# camera_board.net
KiCad netlist of a schematic drawn in EAGLE
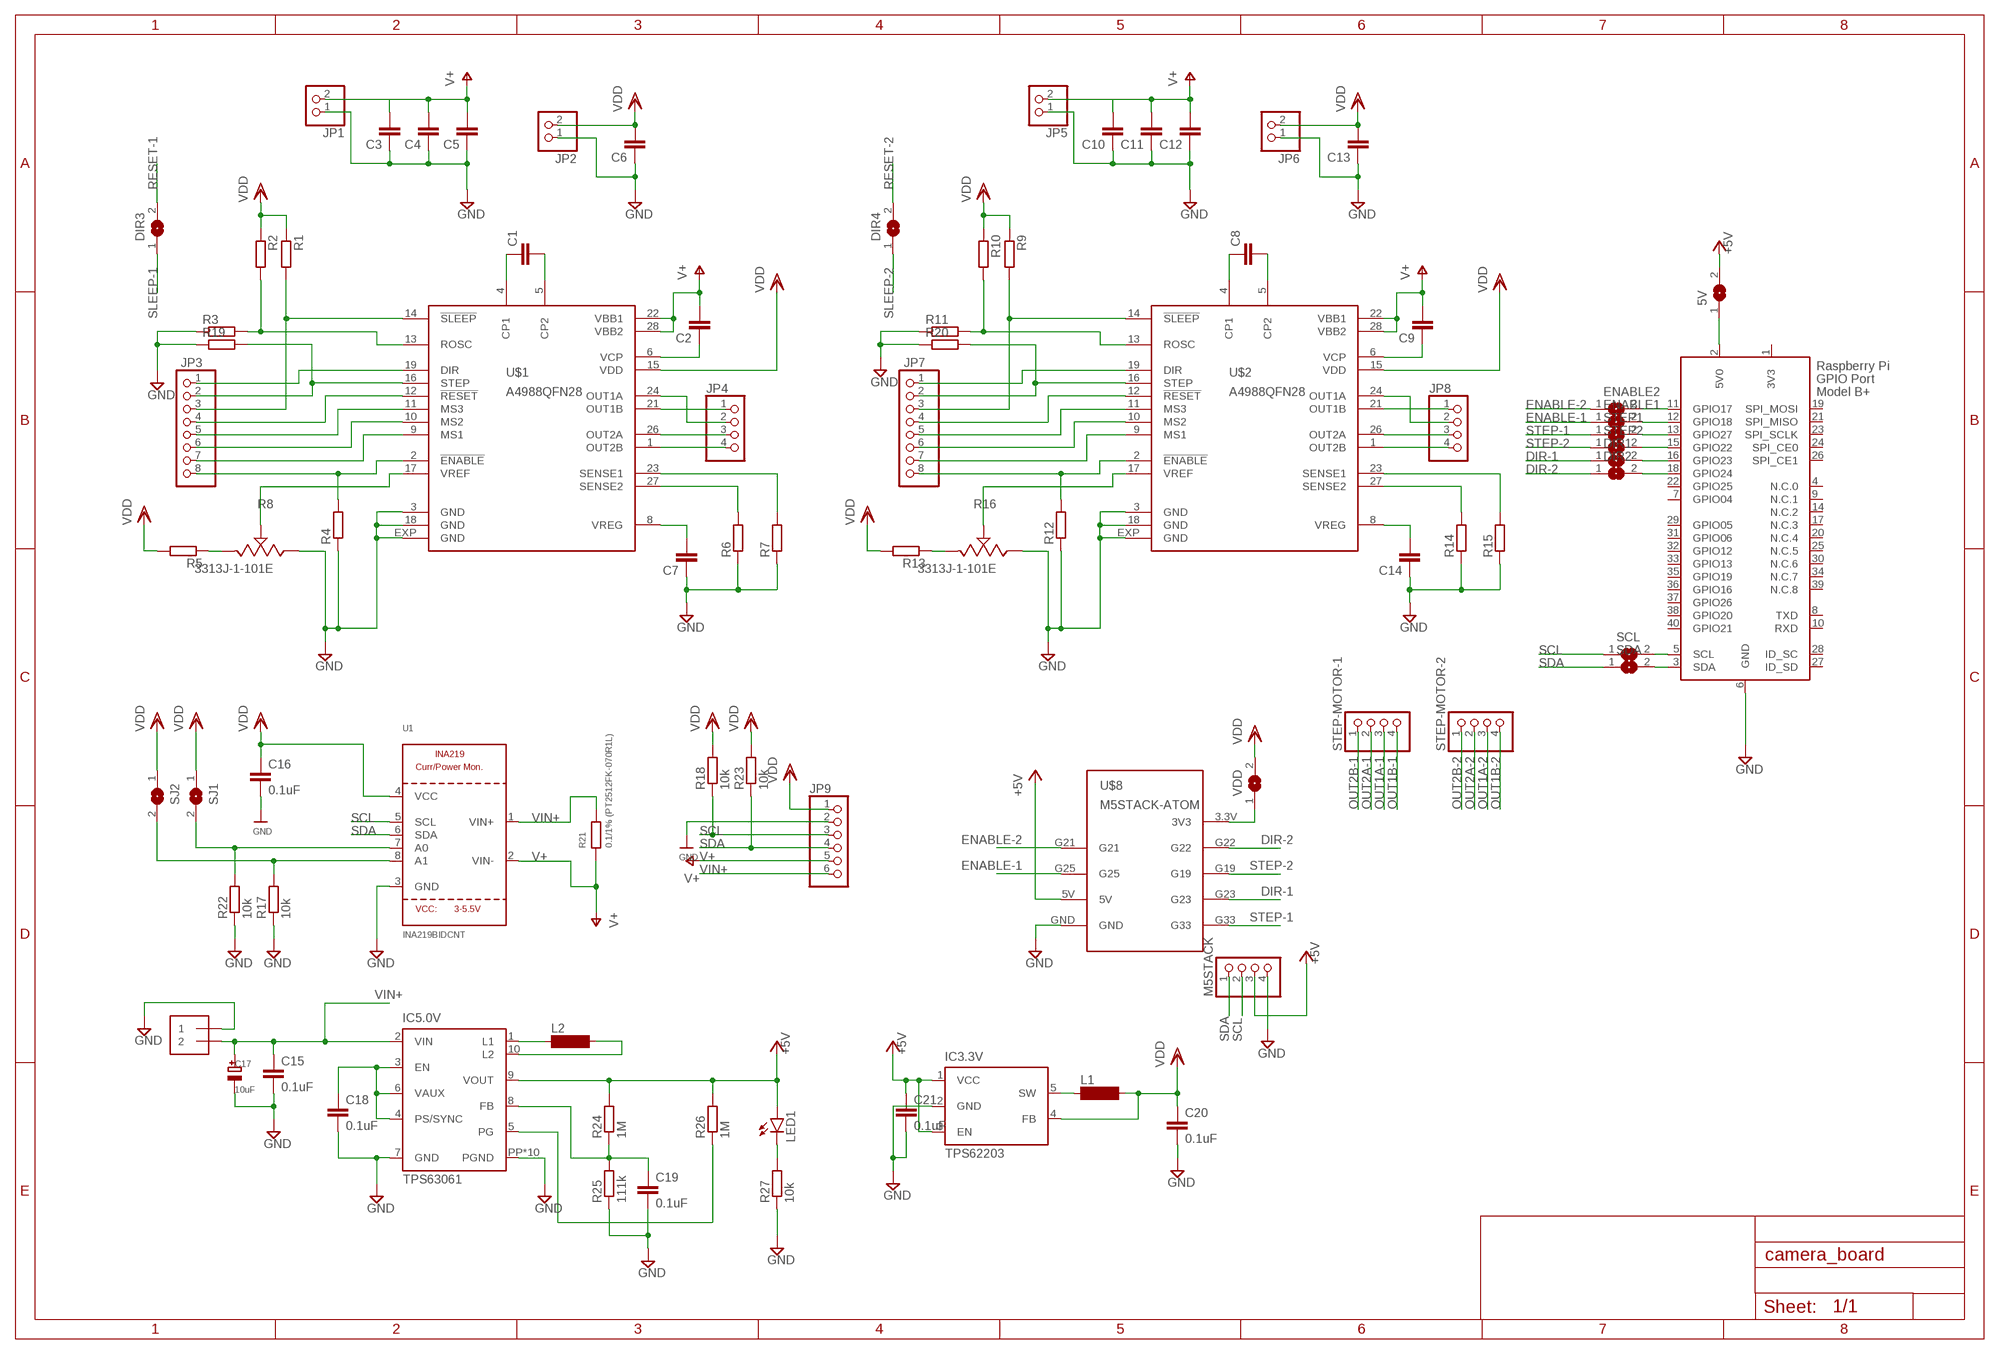
[diagram p0: schematic, sheet 1]

(export (version "E")
  (design (tool "Eeschema 10.0.6"))
  (components
    (comp (ref "5V")
      (value "SOLDERJUMPERREFLOW_NOPASTE")
      (footprint "eagle-import:SOLDERJUMPER_REFLOW_NOPASTE")
      (libsource (lib "eagle-import") (part "SOLDERJUMPERREFLOW_NOPASTE"))
    )
    (comp (ref "7.5V")
      (value "TERMBLOCK_1X2-3.5MM")
      (footprint "eagle-import:1X2-3.5MM")
      (libsource (lib "eagle-import") (part "TERMBLOCK_1X2-3.5MM"))
    )
    (comp (ref "C1")
      (value "C-EUC0402")
      (footprint "eagle-import:C0402")
      (libsource (lib "eagle-import") (part "C-EUC0402"))
    )
    (comp (ref "C2")
      (value "C-EUC0402")
      (footprint "eagle-import:C0402")
      (libsource (lib "eagle-import") (part "C-EUC0402"))
    )
    (comp (ref "C3")
      (value "C-EUC1206")
      (footprint "eagle-import:C1206")
      (libsource (lib "eagle-import") (part "C-EUC1206"))
    )
    (comp (ref "C4")
      (value "C-EUC0402")
      (footprint "eagle-import:C0402")
      (libsource (lib "eagle-import") (part "C-EUC0402"))
    )
    (comp (ref "C5")
      (value "C-EUC0402")
      (footprint "eagle-import:C0402")
      (libsource (lib "eagle-import") (part "C-EUC0402"))
    )
    (comp (ref "C6")
      (value "C-EUC0402")
      (footprint "eagle-import:C0402")
      (libsource (lib "eagle-import") (part "C-EUC0402"))
    )
    (comp (ref "C7")
      (value "C-EUC0402")
      (footprint "eagle-import:C0402")
      (libsource (lib "eagle-import") (part "C-EUC0402"))
    )
    (comp (ref "C8")
      (value "C-EUC0402")
      (footprint "eagle-import:C0402")
      (libsource (lib "eagle-import") (part "C-EUC0402"))
    )
    (comp (ref "C9")
      (value "C-EUC0402")
      (footprint "eagle-import:C0402")
      (libsource (lib "eagle-import") (part "C-EUC0402"))
    )
    (comp (ref "C10")
      (value "C-EUC1206")
      (footprint "eagle-import:C1206")
      (libsource (lib "eagle-import") (part "C-EUC1206"))
    )
    (comp (ref "C11")
      (value "C-EUC0402")
      (footprint "eagle-import:C0402")
      (libsource (lib "eagle-import") (part "C-EUC0402"))
    )
    (comp (ref "C12")
      (value "C-EUC0402")
      (footprint "eagle-import:C0402")
      (libsource (lib "eagle-import") (part "C-EUC0402"))
    )
    (comp (ref "C13")
      (value "C-EUC0402")
      (footprint "eagle-import:C0402")
      (libsource (lib "eagle-import") (part "C-EUC0402"))
    )
    (comp (ref "C14")
      (value "C-EUC0402")
      (footprint "eagle-import:C0402")
      (libsource (lib "eagle-import") (part "C-EUC0402"))
    )
    (comp (ref "C15")
      (value "0.1uF")
      (footprint "eagle-import:C0805")
      (libsource (lib "eagle-import") (part "C-EUC0805"))
    )
    (comp (ref "C16")
      (value "0.1uF")
      (footprint "eagle-import:C0402")
      (libsource (lib "eagle-import") (part "C-EUC0402"))
    )
    (comp (ref "C17")
      (value "10uF")
      (footprint "eagle-import:PANASONIC_C")
      (libsource (lib "eagle-import") (part "CAP_ELECTROLYTICPANASONIC_C"))
    )
    (comp (ref "C18")
      (value "0.1uF")
      (footprint "eagle-import:C0805")
      (libsource (lib "eagle-import") (part "C-EUC0805"))
    )
    (comp (ref "C19")
      (value "0.1uF")
      (footprint "eagle-import:C0805")
      (libsource (lib "eagle-import") (part "C-EUC0805"))
    )
    (comp (ref "C20")
      (value "0.1uF")
      (footprint "eagle-import:C0805")
      (libsource (lib "eagle-import") (part "C-EUC0805"))
    )
    (comp (ref "C21")
      (value "0.1uF")
      (footprint "eagle-import:C0805")
      (libsource (lib "eagle-import") (part "C-EUC0805"))
    )
    (comp (ref "DIR1")
      (value "SOLDERJUMPERREFLOW_NOPASTE")
      (footprint "eagle-import:SOLDERJUMPER_REFLOW_NOPASTE")
      (libsource (lib "eagle-import") (part "SOLDERJUMPERREFLOW_NOPASTE"))
    )
    (comp (ref "DIR2")
      (value "SOLDERJUMPERREFLOW_NOPASTE")
      (footprint "eagle-import:SOLDERJUMPER_REFLOW_NOPASTE")
      (libsource (lib "eagle-import") (part "SOLDERJUMPERREFLOW_NOPASTE"))
    )
    (comp (ref "DIR3")
      (value "SOLDERJUMPERREFLOW_NOPASTE")
      (footprint "eagle-import:SOLDERJUMPER_REFLOW_NOPASTE")
      (libsource (lib "eagle-import") (part "SOLDERJUMPERREFLOW_NOPASTE"))
    )
    (comp (ref "DIR4")
      (value "SOLDERJUMPERREFLOW_NOPASTE")
      (footprint "eagle-import:SOLDERJUMPER_REFLOW_NOPASTE")
      (libsource (lib "eagle-import") (part "SOLDERJUMPERREFLOW_NOPASTE"))
    )
    (comp (ref "ENABLE1")
      (value "SOLDERJUMPERREFLOW_NOPASTE")
      (footprint "eagle-import:SOLDERJUMPER_REFLOW_NOPASTE")
      (libsource (lib "eagle-import") (part "SOLDERJUMPERREFLOW_NOPASTE"))
    )
    (comp (ref "ENABLE2")
      (value "SOLDERJUMPERREFLOW_NOPASTE")
      (footprint "eagle-import:SOLDERJUMPER_REFLOW_NOPASTE")
      (libsource (lib "eagle-import") (part "SOLDERJUMPERREFLOW_NOPASTE"))
    )
    (comp (ref "IC3.3V")
      (value "TPS62203")
      (footprint "eagle-import:SOT23-5")
      (libsource (lib "eagle-import") (part "TPS62203"))
    )
    (comp (ref "IC5.0V")
      (value "TPS63061")
      (footprint "eagle-import:DSC-S-PWSON-N10")
      (libsource (lib "eagle-import") (part "TPS63061"))
    )
    (comp (ref "JP1")
      (value "PINHD-1X2")
      (footprint "eagle-import:1X02")
      (libsource (lib "eagle-import") (part "PINHD-1X2"))
    )
    (comp (ref "JP2")
      (value "PINHD-1X2")
      (footprint "eagle-import:1X02")
      (libsource (lib "eagle-import") (part "PINHD-1X2"))
    )
    (comp (ref "JP3")
      (value "PINHD-1X8")
      (footprint "eagle-import:1X08")
      (libsource (lib "eagle-import") (part "PINHD-1X8"))
    )
    (comp (ref "JP4")
      (value "PINHD-1X4")
      (footprint "eagle-import:1X04")
      (libsource (lib "eagle-import") (part "PINHD-1X4"))
    )
    (comp (ref "JP5")
      (value "PINHD-1X2")
      (footprint "eagle-import:1X02")
      (libsource (lib "eagle-import") (part "PINHD-1X2"))
    )
    (comp (ref "JP6")
      (value "PINHD-1X2")
      (footprint "eagle-import:1X02")
      (libsource (lib "eagle-import") (part "PINHD-1X2"))
    )
    (comp (ref "JP7")
      (value "PINHD-1X8")
      (footprint "eagle-import:1X08")
      (libsource (lib "eagle-import") (part "PINHD-1X8"))
    )
    (comp (ref "JP8")
      (value "PINHD-1X4")
      (footprint "eagle-import:1X04")
      (libsource (lib "eagle-import") (part "PINHD-1X4"))
    )
    (comp (ref "JP9")
      (value "HEADER-1X670MIL")
      (footprint "eagle-import:1X06_ROUND_70")
      (libsource (lib "eagle-import") (part "HEADER-1X670MIL"))
    )
    (comp (ref "L1")
      (value "MS50")
      (footprint "eagle-import:MS50")
      (libsource (lib "eagle-import") (part "MS50"))
    )
    (comp (ref "L2")
      (value "MS50")
      (footprint "eagle-import:MS50")
      (libsource (lib "eagle-import") (part "MS50"))
    )
    (comp (ref "LED1")
      (value "LEDCHIPLED_0603")
      (footprint "eagle-import:CHIPLED_0603")
      (libsource (lib "eagle-import") (part "LEDCHIPLED_0603"))
    )
    (comp (ref "M5STACK")
      (value "PINHD-1X4")
      (footprint "eagle-import:1X04")
      (libsource (lib "eagle-import") (part "PINHD-1X4"))
    )
    (comp (ref "R1")
      (value "R-EU_R0402")
      (footprint "eagle-import:R0402")
      (libsource (lib "eagle-import") (part "R-EU_R0402"))
    )
    (comp (ref "R2")
      (value "R-EU_R0402")
      (footprint "eagle-import:R0402")
      (libsource (lib "eagle-import") (part "R-EU_R0402"))
    )
    (comp (ref "R3")
      (value "R-EU_R0402")
      (footprint "eagle-import:R0402")
      (libsource (lib "eagle-import") (part "R-EU_R0402"))
    )
    (comp (ref "R4")
      (value "R-EU_R0402")
      (footprint "eagle-import:R0402")
      (libsource (lib "eagle-import") (part "R-EU_R0402"))
    )
    (comp (ref "R5")
      (value "R-EU_R0402")
      (footprint "eagle-import:R0402")
      (libsource (lib "eagle-import") (part "R-EU_R0402"))
    )
    (comp (ref "R6")
      (value "R-EU_R0603")
      (footprint "eagle-import:R0603")
      (libsource (lib "eagle-import") (part "R-EU_R0603"))
    )
    (comp (ref "R7")
      (value "R-EU_R0603")
      (footprint "eagle-import:R0603")
      (libsource (lib "eagle-import") (part "R-EU_R0603"))
    )
    (comp (ref "R8")
      (value "3313J-1-101E")
      (footprint "eagle-import:3313J-1-101E")
      (fields (field (name "MANUFACTURER") "Bourns Inc.") (field (name "CREATED_BY") "PCBLayout.com"))
      (libsource (lib "eagle-import") (part "3313J-1-101E"))
    )
    (comp (ref "R9")
      (value "R-EU_R0402")
      (footprint "eagle-import:R0402")
      (libsource (lib "eagle-import") (part "R-EU_R0402"))
    )
    (comp (ref "R10")
      (value "R-EU_R0402")
      (footprint "eagle-import:R0402")
      (libsource (lib "eagle-import") (part "R-EU_R0402"))
    )
    (comp (ref "R11")
      (value "R-EU_R0402")
      (footprint "eagle-import:R0402")
      (libsource (lib "eagle-import") (part "R-EU_R0402"))
    )
    (comp (ref "R12")
      (value "R-EU_R0402")
      (footprint "eagle-import:R0402")
      (libsource (lib "eagle-import") (part "R-EU_R0402"))
    )
    (comp (ref "R13")
      (value "R-EU_R0402")
      (footprint "eagle-import:R0402")
      (libsource (lib "eagle-import") (part "R-EU_R0402"))
    )
    (comp (ref "R14")
      (value "R-EU_R0603")
      (footprint "eagle-import:R0603")
      (libsource (lib "eagle-import") (part "R-EU_R0603"))
    )
    (comp (ref "R15")
      (value "R-EU_R0603")
      (footprint "eagle-import:R0603")
      (libsource (lib "eagle-import") (part "R-EU_R0603"))
    )
    (comp (ref "R16")
      (value "3313J-1-101E")
      (footprint "eagle-import:3313J-1-101E")
      (fields (field (name "MANUFACTURER") "Bourns Inc.") (field (name "CREATED_BY") "PCBLayout.com"))
      (libsource (lib "eagle-import") (part "3313J-1-101E"))
    )
    (comp (ref "R17")
      (value "10k")
      (footprint "eagle-import:R0603")
      (libsource (lib "eagle-import") (part "R-EU_R0603"))
    )
    (comp (ref "R18")
      (value "10k")
      (footprint "eagle-import:R0603")
      (libsource (lib "eagle-import") (part "R-EU_R0603"))
    )
    (comp (ref "R19")
      (value "R-EU_R0805")
      (footprint "eagle-import:R0805")
      (libsource (lib "eagle-import") (part "R-EU_R0805"))
    )
    (comp (ref "R20")
      (value "R-EU_R0805")
      (footprint "eagle-import:R0805")
      (libsource (lib "eagle-import") (part "R-EU_R0805"))
    )
    (comp (ref "R21")
      (value "0.1/1% (PT2512FK-070R1L)")
      (footprint "eagle-import:R2512")
      (libsource (lib "eagle-import") (part "R-EU_R2512"))
    )
    (comp (ref "R22")
      (value "10k")
      (footprint "eagle-import:R0603")
      (libsource (lib "eagle-import") (part "R-EU_R0603"))
    )
    (comp (ref "R23")
      (value "10k")
      (footprint "eagle-import:R0603")
      (libsource (lib "eagle-import") (part "R-EU_R0603"))
    )
    (comp (ref "R24")
      (value "1M")
      (footprint "eagle-import:R0603")
      (libsource (lib "eagle-import") (part "R-EU_R0603"))
    )
    (comp (ref "R25")
      (value "111k")
      (footprint "eagle-import:R0603")
      (libsource (lib "eagle-import") (part "R-EU_R0603"))
    )
    (comp (ref "R26")
      (value "1M")
      (footprint "eagle-import:R0603")
      (libsource (lib "eagle-import") (part "R-EU_R0603"))
    )
    (comp (ref "R27")
      (value "10k")
      (footprint "eagle-import:R0603")
      (libsource (lib "eagle-import") (part "R-EU_R0603"))
    )
    (comp (ref "SCL")
      (value "SOLDERJUMPERREFLOW_NOPASTE")
      (footprint "eagle-import:SOLDERJUMPER_REFLOW_NOPASTE")
      (libsource (lib "eagle-import") (part "SOLDERJUMPERREFLOW_NOPASTE"))
    )
    (comp (ref "SDA")
      (value "SOLDERJUMPERREFLOW_NOPASTE")
      (footprint "eagle-import:SOLDERJUMPER_REFLOW_NOPASTE")
      (libsource (lib "eagle-import") (part "SOLDERJUMPERREFLOW_NOPASTE"))
    )
    (comp (ref "SJ1")
      (value "SOLDERJUMPERREFLOW_NOPASTE")
      (footprint "eagle-import:SOLDERJUMPER_REFLOW_NOPASTE")
      (libsource (lib "eagle-import") (part "SOLDERJUMPERREFLOW_NOPASTE"))
    )
    (comp (ref "SJ2")
      (value "SOLDERJUMPERREFLOW_NOPASTE")
      (footprint "eagle-import:SOLDERJUMPER_REFLOW_NOPASTE")
      (libsource (lib "eagle-import") (part "SOLDERJUMPERREFLOW_NOPASTE"))
    )
    (comp (ref "STEP-MOTOR-1")
      (value "PINHD-1X4")
      (footprint "eagle-import:1X04")
      (libsource (lib "eagle-import") (part "PINHD-1X4"))
    )
    (comp (ref "STEP-MOTOR-2")
      (value "PINHD-1X4")
      (footprint "eagle-import:1X04")
      (libsource (lib "eagle-import") (part "PINHD-1X4"))
    )
    (comp (ref "STEP1")
      (value "SOLDERJUMPERREFLOW_NOPASTE")
      (footprint "eagle-import:SOLDERJUMPER_REFLOW_NOPASTE")
      (libsource (lib "eagle-import") (part "SOLDERJUMPERREFLOW_NOPASTE"))
    )
    (comp (ref "STEP2")
      (value "SOLDERJUMPERREFLOW_NOPASTE")
      (footprint "eagle-import:SOLDERJUMPER_REFLOW_NOPASTE")
      (libsource (lib "eagle-import") (part "SOLDERJUMPERREFLOW_NOPASTE"))
    )
    (comp (ref "U$1")
      (value "A4988QFN28")
      (footprint "eagle-import:QFN28-ML_6X6MM")
      (libsource (lib "eagle-import") (part "A4988QFN28"))
    )
    (comp (ref "U$2")
      (value "A4988QFN28")
      (footprint "eagle-import:QFN28-ML_6X6MM")
      (libsource (lib "eagle-import") (part "A4988QFN28"))
    )
    (comp (ref "U$8")
      (value "M5STACK-ATOM")
      (footprint "eagle-import:M5STACK-ATOM")
      (libsource (lib "eagle-import") (part "M5STACK-ATOM"))
    )
    (comp (ref "U1")
      (value "INA219BIDCNT")
      (footprint "eagle-import:SOT23-8")
      (libsource (lib "eagle-import") (part "INA219"))
    )
    (comp (ref "VDD")
      (value "SOLDERJUMPERREFLOW_NOPASTE")
      (footprint "eagle-import:SOLDERJUMPER_REFLOW_NOPASTE")
      (libsource (lib "eagle-import") (part "SOLDERJUMPERREFLOW_NOPASTE"))
    )
    (comp (ref "X1")
      (value "RASPI_BOARD_B+_E4")
      (footprint "eagle-import:RASPI_BOARD_B+_EDGES_4DRILL")
      (libsource (lib "eagle-import") (part "RASPI_BOARD_B+_E4"))
    )
  )
  (nets
    (net (code "1") (name "+5V") (class "Default")
      (node (ref "5V") (pin "2") (pinfunction "2_2") (pintype "passive"))
      (node (ref "C21") (pin "1") (pinfunction "1_1") (pintype "passive"))
      (node (ref "IC3.3V") (pin "1") (pinfunction "VCC_1") (pintype "power_in"))
      (node (ref "IC3.3V") (pin "3") (pinfunction "EN_3") (pintype "input"))
      (node (ref "IC5.0V") (pin "9") (pinfunction "VOUT_9") (pintype "output"))
      (node (ref "LED1") (pin "A") (pinfunction "A_A") (pintype "passive"))
      (node (ref "M5STACK") (pin "3") (pinfunction "3_3") (pintype "passive"))
      (node (ref "R24") (pin "2") (pinfunction "2_2") (pintype "passive"))
      (node (ref "R26") (pin "2") (pinfunction "2_2") (pintype "passive"))
      (node (ref "U$8") (pin "5V") (pinfunction "5V_5V") (pintype "bidirectional"))
    )
    (net (code "2") (name "/3V3") (class "Default")
      (node (ref "X1") (pin "1") (pinfunction "3V3_1") (pintype "power_in"))
    )
    (net (code "3") (name "/DIR-1") (class "Default")
      (node (ref "DIR1") (pin "1") (pinfunction "1_1") (pintype "passive"))
      (node (ref "JP3") (pin "1") (pinfunction "1_1") (pintype "passive"))
      (node (ref "U$1") (pin "19") (pinfunction "DIR_19") (pintype "bidirectional"))
      (node (ref "U$8") (pin "G23") (pinfunction "G23_G23") (pintype "bidirectional"))
    )
    (net (code "4") (name "/DIR-2") (class "Default")
      (node (ref "DIR2") (pin "1") (pinfunction "1_1") (pintype "passive"))
      (node (ref "JP7") (pin "1") (pinfunction "1_1") (pintype "passive"))
      (node (ref "U$2") (pin "19") (pinfunction "DIR_19") (pintype "bidirectional"))
      (node (ref "U$8") (pin "G22") (pinfunction "G22_G22") (pintype "bidirectional"))
    )
    (net (code "5") (name "/ENABLE-1") (class "Default")
      (node (ref "ENABLE1") (pin "1") (pinfunction "1_1") (pintype "passive"))
      (node (ref "JP3") (pin "8") (pinfunction "8_8") (pintype "passive"))
      (node (ref "R4") (pin "2") (pinfunction "2_2") (pintype "passive"))
      (node (ref "U$1") (pin "2") (pinfunction "~{ENABLE}_2") (pintype "bidirectional"))
      (node (ref "U$8") (pin "G25") (pinfunction "G25_G25") (pintype "bidirectional"))
    )
    (net (code "6") (name "/ENABLE-2") (class "Default")
      (node (ref "ENABLE2") (pin "1") (pinfunction "1_1") (pintype "passive"))
      (node (ref "JP7") (pin "8") (pinfunction "8_8") (pintype "passive"))
      (node (ref "R12") (pin "2") (pinfunction "2_2") (pintype "passive"))
      (node (ref "U$2") (pin "2") (pinfunction "~{ENABLE}_2") (pintype "bidirectional"))
      (node (ref "U$8") (pin "G21") (pinfunction "G21_G21") (pintype "bidirectional"))
    )
    (net (code "7") (name "/OUT1A-1") (class "Default")
      (node (ref "JP4") (pin "2") (pinfunction "2_2") (pintype "passive"))
      (node (ref "STEP-MOTOR-1") (pin "3") (pinfunction "3_3") (pintype "passive"))
      (node (ref "U$1") (pin "24") (pinfunction "OUT1A_24") (pintype "output"))
    )
    (net (code "8") (name "/OUT1A-2") (class "Default")
      (node (ref "JP8") (pin "2") (pinfunction "2_2") (pintype "passive"))
      (node (ref "STEP-MOTOR-2") (pin "3") (pinfunction "3_3") (pintype "passive"))
      (node (ref "U$2") (pin "24") (pinfunction "OUT1A_24") (pintype "output"))
    )
    (net (code "9") (name "/OUT1B-1") (class "Default")
      (node (ref "JP4") (pin "1") (pinfunction "1_1") (pintype "passive"))
      (node (ref "STEP-MOTOR-1") (pin "4") (pinfunction "4_4") (pintype "passive"))
      (node (ref "U$1") (pin "21") (pinfunction "OUT1B_21") (pintype "output"))
    )
    (net (code "10") (name "/OUT1B-2") (class "Default")
      (node (ref "JP8") (pin "1") (pinfunction "1_1") (pintype "passive"))
      (node (ref "STEP-MOTOR-2") (pin "4") (pinfunction "4_4") (pintype "passive"))
      (node (ref "U$2") (pin "21") (pinfunction "OUT1B_21") (pintype "output"))
    )
    (net (code "11") (name "/OUT2A-1") (class "Default")
      (node (ref "JP4") (pin "3") (pinfunction "3_3") (pintype "passive"))
      (node (ref "STEP-MOTOR-1") (pin "2") (pinfunction "2_2") (pintype "passive"))
      (node (ref "U$1") (pin "26") (pinfunction "OUT2A_26") (pintype "output"))
    )
    (net (code "12") (name "/OUT2A-2") (class "Default")
      (node (ref "JP8") (pin "3") (pinfunction "3_3") (pintype "passive"))
      (node (ref "STEP-MOTOR-2") (pin "2") (pinfunction "2_2") (pintype "passive"))
      (node (ref "U$2") (pin "26") (pinfunction "OUT2A_26") (pintype "output"))
    )
    (net (code "13") (name "/OUT2B-1") (class "Default")
      (node (ref "JP4") (pin "4") (pinfunction "4_4") (pintype "passive"))
      (node (ref "STEP-MOTOR-1") (pin "1") (pinfunction "1_1") (pintype "passive"))
      (node (ref "U$1") (pin "1") (pinfunction "OUT2B_1") (pintype "output"))
    )
    (net (code "14") (name "/OUT2B-2") (class "Default")
      (node (ref "JP8") (pin "4") (pinfunction "4_4") (pintype "passive"))
      (node (ref "STEP-MOTOR-2") (pin "1") (pinfunction "1_1") (pintype "passive"))
      (node (ref "U$2") (pin "1") (pinfunction "OUT2B_1") (pintype "output"))
    )
    (net (code "15") (name "/RESET-1") (class "Default")
      (node (ref "DIR3") (pin "2") (pinfunction "2_2") (pintype "passive"))
      (node (ref "JP3") (pin "4") (pinfunction "4_4") (pintype "passive"))
      (node (ref "U$1") (pin "12") (pinfunction "~{RESET}_12") (pintype "bidirectional"))
    )
    (net (code "16") (name "/RESET-2") (class "Default")
      (node (ref "DIR4") (pin "2") (pinfunction "2_2") (pintype "passive"))
      (node (ref "JP7") (pin "4") (pinfunction "4_4") (pintype "passive"))
      (node (ref "U$2") (pin "12") (pinfunction "~{RESET}_12") (pintype "bidirectional"))
    )
    (net (code "17") (name "/SCL") (class "Default")
      (node (ref "JP9") (pin "3") (pinfunction "3_3") (pintype "passive"))
      (node (ref "M5STACK") (pin "2") (pinfunction "2_2") (pintype "passive"))
      (node (ref "R18") (pin "1") (pinfunction "1_1") (pintype "passive"))
      (node (ref "SCL") (pin "1") (pinfunction "1_1") (pintype "passive"))
      (node (ref "U1") (pin "5") (pinfunction "SCL_5") (pintype "bidirectional"))
    )
    (net (code "18") (name "/SDA") (class "Default")
      (node (ref "JP9") (pin "4") (pinfunction "4_4") (pintype "passive"))
      (node (ref "M5STACK") (pin "1") (pinfunction "1_1") (pintype "passive"))
      (node (ref "R23") (pin "1") (pinfunction "1_1") (pintype "passive"))
      (node (ref "SDA") (pin "1") (pinfunction "1_1") (pintype "passive"))
      (node (ref "U1") (pin "6") (pinfunction "SDA_6") (pintype "bidirectional"))
    )
    (net (code "19") (name "/SLEEP-1") (class "Default")
      (node (ref "DIR3") (pin "1") (pinfunction "1_1") (pintype "passive"))
      (node (ref "JP3") (pin "3") (pinfunction "3_3") (pintype "passive"))
      (node (ref "R1") (pin "2") (pinfunction "2_2") (pintype "passive"))
      (node (ref "U$1") (pin "14") (pinfunction "~{SLEEP}_14") (pintype "bidirectional"))
    )
    (net (code "20") (name "/SLEEP-2") (class "Default")
      (node (ref "DIR4") (pin "1") (pinfunction "1_1") (pintype "passive"))
      (node (ref "JP7") (pin "3") (pinfunction "3_3") (pintype "passive"))
      (node (ref "R9") (pin "2") (pinfunction "2_2") (pintype "passive"))
      (node (ref "U$2") (pin "14") (pinfunction "~{SLEEP}_14") (pintype "bidirectional"))
    )
    (net (code "21") (name "/STEP-1") (class "Default")
      (node (ref "JP3") (pin "2") (pinfunction "2_2") (pintype "passive"))
      (node (ref "R19") (pin "2") (pinfunction "2_2") (pintype "passive"))
      (node (ref "STEP1") (pin "1") (pinfunction "1_1") (pintype "passive"))
      (node (ref "U$1") (pin "16") (pinfunction "STEP_16") (pintype "output"))
      (node (ref "U$8") (pin "G33") (pinfunction "G33_G33") (pintype "bidirectional"))
    )
    (net (code "22") (name "/STEP-2") (class "Default")
      (node (ref "JP7") (pin "2") (pinfunction "2_2") (pintype "passive"))
      (node (ref "R20") (pin "2") (pinfunction "2_2") (pintype "passive"))
      (node (ref "STEP2") (pin "1") (pinfunction "1_1") (pintype "passive"))
      (node (ref "U$2") (pin "16") (pinfunction "STEP_16") (pintype "output"))
      (node (ref "U$8") (pin "G19") (pinfunction "G19_G19") (pintype "bidirectional"))
    )
    (net (code "23") (name "/VIN+") (class "Default")
      (node (ref "7.5V") (pin "2") (pinfunction "2_2") (pintype "passive"))
      (node (ref "C15") (pin "1") (pinfunction "1_1") (pintype "passive"))
      (node (ref "C17") (pin "+") (pinfunction "+_+") (pintype "passive"))
      (node (ref "IC5.0V") (pin "2") (pinfunction "VIN_2") (pintype "input"))
      (node (ref "JP9") (pin "6") (pinfunction "6_6") (pintype "passive"))
      (node (ref "R21") (pin "2") (pinfunction "2_2") (pintype "passive"))
      (node (ref "U1") (pin "1") (pinfunction "VIN+_1") (pintype "bidirectional"))
    )
    (net (code "24") (name "GND") (class "Default")
      (node (ref "7.5V") (pin "1") (pinfunction "1_1") (pintype "passive"))
      (node (ref "C10") (pin "1") (pinfunction "1_1") (pintype "passive"))
      (node (ref "C11") (pin "1") (pinfunction "1_1") (pintype "passive"))
      (node (ref "C12") (pin "1") (pinfunction "1_1") (pintype "passive"))
      (node (ref "C13") (pin "1") (pinfunction "1_1") (pintype "passive"))
      (node (ref "C14") (pin "1") (pinfunction "1_1") (pintype "passive"))
      (node (ref "C15") (pin "2") (pinfunction "2_2") (pintype "passive"))
      (node (ref "C16") (pin "2") (pinfunction "2_2") (pintype "passive"))
      (node (ref "C17") (pin "-") (pinfunction "-_-") (pintype "passive"))
      (node (ref "C18") (pin "2") (pinfunction "2_2") (pintype "passive"))
      (node (ref "C19") (pin "2") (pinfunction "2_2") (pintype "passive"))
      (node (ref "C20") (pin "2") (pinfunction "2_2") (pintype "passive"))
      (node (ref "C21") (pin "2") (pinfunction "2_2") (pintype "passive"))
      (node (ref "C3") (pin "1") (pinfunction "1_1") (pintype "passive"))
      (node (ref "C4") (pin "1") (pinfunction "1_1") (pintype "passive"))
      (node (ref "C5") (pin "1") (pinfunction "1_1") (pintype "passive"))
      (node (ref "C6") (pin "1") (pinfunction "1_1") (pintype "passive"))
      (node (ref "C7") (pin "1") (pinfunction "1_1") (pintype "passive"))
      (node (ref "IC3.3V") (pin "2") (pinfunction "GND_2") (pintype "power_in"))
      (node (ref "IC5.0V") (pin "7") (pinfunction "GND_7") (pintype "input"))
      (node (ref "IC5.0V") (pin "PP") (pinfunction "PGND_PP") (pintype "power_in"))
      (node (ref "IC5.0V") (pin "PP@1") (pinfunction "PGND_PP@1") (pintype "power_in"))
      (node (ref "IC5.0V") (pin "PP@10") (pinfunction "PGND_PP@10") (pintype "power_in"))
      (node (ref "IC5.0V") (pin "PP@2") (pinfunction "PGND_PP@2") (pintype "power_in"))
      (node (ref "IC5.0V") (pin "PP@3") (pinfunction "PGND_PP@3") (pintype "power_in"))
      (node (ref "IC5.0V") (pin "PP@4") (pinfunction "PGND_PP@4") (pintype "power_in"))
      (node (ref "IC5.0V") (pin "PP@5") (pinfunction "PGND_PP@5") (pintype "power_in"))
      (node (ref "IC5.0V") (pin "PP@7") (pinfunction "PGND_PP@7") (pintype "power_in"))
      (node (ref "IC5.0V") (pin "PP@8") (pinfunction "PGND_PP@8") (pintype "power_in"))
      (node (ref "IC5.0V") (pin "PP@9") (pinfunction "PGND_PP@9") (pintype "power_in"))
      (node (ref "JP1") (pin "1") (pinfunction "1_1") (pintype "passive"))
      (node (ref "JP2") (pin "1") (pinfunction "1_1") (pintype "passive"))
      (node (ref "JP5") (pin "1") (pinfunction "1_1") (pintype "passive"))
      (node (ref "JP6") (pin "1") (pinfunction "1_1") (pintype "passive"))
      (node (ref "JP9") (pin "2") (pinfunction "2_2") (pintype "passive"))
      (node (ref "M5STACK") (pin "4") (pinfunction "4_4") (pintype "passive"))
      (node (ref "R11") (pin "1") (pinfunction "1_1") (pintype "passive"))
      (node (ref "R12") (pin "1") (pinfunction "1_1") (pintype "passive"))
      (node (ref "R14") (pin "1") (pinfunction "1_1") (pintype "passive"))
      (node (ref "R15") (pin "1") (pinfunction "1_1") (pintype "passive"))
      (node (ref "R16") (pin "3") (pinfunction "3_3") (pintype "passive"))
      (node (ref "R17") (pin "1") (pinfunction "1_1") (pintype "passive"))
      (node (ref "R19") (pin "1") (pinfunction "1_1") (pintype "passive"))
      (node (ref "R20") (pin "1") (pinfunction "1_1") (pintype "passive"))
      (node (ref "R22") (pin "1") (pinfunction "1_1") (pintype "passive"))
      (node (ref "R25") (pin "1") (pinfunction "1_1") (pintype "passive"))
      (node (ref "R27") (pin "1") (pinfunction "1_1") (pintype "passive"))
      (node (ref "R3") (pin "1") (pinfunction "1_1") (pintype "passive"))
      (node (ref "R4") (pin "1") (pinfunction "1_1") (pintype "passive"))
      (node (ref "R6") (pin "1") (pinfunction "1_1") (pintype "passive"))
      (node (ref "R7") (pin "1") (pinfunction "1_1") (pintype "passive"))
      (node (ref "R8") (pin "3") (pinfunction "3_3") (pintype "passive"))
      (node (ref "U$1") (pin "18") (pinfunction "GND_18") (pintype "power_in"))
      (node (ref "U$1") (pin "3") (pinfunction "GND_3") (pintype "power_in"))
      (node (ref "U$1") (pin "EXP") (pinfunction "GND_EXP") (pintype "power_in"))
      (node (ref "U$2") (pin "18") (pinfunction "GND_18") (pintype "power_in"))
      (node (ref "U$2") (pin "3") (pinfunction "GND_3") (pintype "power_in"))
      (node (ref "U$2") (pin "EXP") (pinfunction "GND_EXP") (pintype "power_in"))
      (node (ref "U$8") (pin "GND") (pinfunction "GND_GND") (pintype "bidirectional"))
      (node (ref "U1") (pin "3") (pinfunction "GND_3") (pintype "bidirectional"))
      (node (ref "X1") (pin "6") (pinfunction "GND_6") (pintype "power_in"))
    )
    (net (code "25") (name "Net-(IC3.3V-SW)") (class "Default")
      (node (ref "IC3.3V") (pin "5") (pinfunction "SW_5") (pintype "output"))
      (node (ref "L1") (pin "1") (pinfunction "1_1") (pintype "passive"))
    )
    (net (code "26") (name "Net-(IC5.0V-EN)") (class "Default")
      (node (ref "C18") (pin "1") (pinfunction "1_1") (pintype "passive"))
      (node (ref "IC5.0V") (pin "3") (pinfunction "EN_3") (pintype "input"))
      (node (ref "IC5.0V") (pin "4") (pinfunction "PS/SYNC_4") (pintype "input"))
      (node (ref "IC5.0V") (pin "6") (pinfunction "VAUX_6") (pintype "power_in"))
    )
    (net (code "27") (name "Net-(IC5.0V-FB)") (class "Default")
      (node (ref "C19") (pin "1") (pinfunction "1_1") (pintype "passive"))
      (node (ref "IC5.0V") (pin "8") (pinfunction "FB_8") (pintype "input"))
      (node (ref "R24") (pin "1") (pinfunction "1_1") (pintype "passive"))
      (node (ref "R25") (pin "2") (pinfunction "2_2") (pintype "passive"))
    )
    (net (code "28") (name "Net-(IC5.0V-L1)") (class "Default")
      (node (ref "IC5.0V") (pin "1") (pinfunction "L1_1") (pintype "input"))
      (node (ref "L2") (pin "1") (pinfunction "1_1") (pintype "passive"))
    )
    (net (code "29") (name "Net-(IC5.0V-L2)") (class "Default")
      (node (ref "IC5.0V") (pin "10") (pinfunction "L2_10") (pintype "input"))
      (node (ref "L2") (pin "2") (pinfunction "2_2") (pintype "passive"))
    )
    (net (code "30") (name "Net-(IC5.0V-PG)") (class "Default")
      (node (ref "IC5.0V") (pin "5") (pinfunction "PG_5") (pintype "output"))
      (node (ref "R26") (pin "1") (pinfunction "1_1") (pintype "passive"))
    )
    (net (code "31") (name "Net-(LED1-PadC)") (class "Default")
      (node (ref "LED1") (pin "C") (pinfunction "C_C") (pintype "passive"))
      (node (ref "R27") (pin "2") (pinfunction "2_2") (pintype "passive"))
    )
    (net (code "32") (name "Net-(R5-Pad1)") (class "Default")
      (node (ref "R5") (pin "1") (pinfunction "1_1") (pintype "passive"))
      (node (ref "R8") (pin "1") (pinfunction "1_1") (pintype "passive"))
    )
    (net (code "33") (name "Net-(R13-Pad1)") (class "Default")
      (node (ref "R13") (pin "1") (pinfunction "1_1") (pintype "passive"))
      (node (ref "R16") (pin "1") (pinfunction "1_1") (pintype "passive"))
    )
    (net (code "34") (name "Net-(U$1-CP1)") (class "Default")
      (node (ref "C1") (pin "1") (pinfunction "1_1") (pintype "passive"))
      (node (ref "U$1") (pin "4") (pinfunction "CP1_4") (pintype "bidirectional"))
    )
    (net (code "35") (name "Net-(U$1-CP2)") (class "Default")
      (node (ref "C1") (pin "2") (pinfunction "2_2") (pintype "passive"))
      (node (ref "U$1") (pin "5") (pinfunction "CP2_5") (pintype "bidirectional"))
    )
    (net (code "36") (name "Net-(U$1-MS1)") (class "Default")
      (node (ref "JP3") (pin "7") (pinfunction "7_7") (pintype "passive"))
      (node (ref "U$1") (pin "9") (pinfunction "MS1_9") (pintype "bidirectional"))
    )
    (net (code "37") (name "Net-(U$1-MS2)") (class "Default")
      (node (ref "JP3") (pin "6") (pinfunction "6_6") (pintype "passive"))
      (node (ref "U$1") (pin "10") (pinfunction "MS2_10") (pintype "input"))
    )
    (net (code "38") (name "Net-(U$1-MS3)") (class "Default")
      (node (ref "JP3") (pin "5") (pinfunction "5_5") (pintype "passive"))
      (node (ref "U$1") (pin "11") (pinfunction "MS3_11") (pintype "bidirectional"))
    )
    (net (code "39") (name "Net-(U$1-ROSC)") (class "Default")
      (node (ref "R2") (pin "2") (pinfunction "2_2") (pintype "passive"))
      (node (ref "R3") (pin "2") (pinfunction "2_2") (pintype "passive"))
      (node (ref "U$1") (pin "13") (pinfunction "ROSC_13") (pintype "bidirectional"))
    )
    (net (code "40") (name "Net-(U$1-SENSE1)") (class "Default")
      (node (ref "R7") (pin "2") (pinfunction "2_2") (pintype "passive"))
      (node (ref "U$1") (pin "23") (pinfunction "SENSE1_23") (pintype "input"))
    )
    (net (code "41") (name "Net-(U$1-SENSE2)") (class "Default")
      (node (ref "R6") (pin "2") (pinfunction "2_2") (pintype "passive"))
      (node (ref "U$1") (pin "27") (pinfunction "SENSE2_27") (pintype "bidirectional"))
    )
    (net (code "42") (name "Net-(U$1-VCP)") (class "Default")
      (node (ref "C2") (pin "1") (pinfunction "1_1") (pintype "passive"))
      (node (ref "U$1") (pin "6") (pinfunction "VCP_6") (pintype "power_in"))
    )
    (net (code "43") (name "Net-(U$1-VREF)") (class "Default")
      (node (ref "R8") (pin "2") (pinfunction "2_2") (pintype "passive"))
      (node (ref "U$1") (pin "17") (pinfunction "VREF_17") (pintype "power_in"))
    )
    (net (code "44") (name "Net-(U$1-VREG)") (class "Default")
      (node (ref "C7") (pin "2") (pinfunction "2_2") (pintype "passive"))
      (node (ref "U$1") (pin "8") (pinfunction "VREG_8") (pintype "power_in"))
    )
    (net (code "45") (name "Net-(U$2-CP1)") (class "Default")
      (node (ref "C8") (pin "1") (pinfunction "1_1") (pintype "passive"))
      (node (ref "U$2") (pin "4") (pinfunction "CP1_4") (pintype "bidirectional"))
    )
    (net (code "46") (name "Net-(U$2-CP2)") (class "Default")
      (node (ref "C8") (pin "2") (pinfunction "2_2") (pintype "passive"))
      (node (ref "U$2") (pin "5") (pinfunction "CP2_5") (pintype "bidirectional"))
    )
    (net (code "47") (name "Net-(U$2-MS1)") (class "Default")
      (node (ref "JP7") (pin "7") (pinfunction "7_7") (pintype "passive"))
      (node (ref "U$2") (pin "9") (pinfunction "MS1_9") (pintype "bidirectional"))
    )
    (net (code "48") (name "Net-(U$2-MS2)") (class "Default")
      (node (ref "JP7") (pin "6") (pinfunction "6_6") (pintype "passive"))
      (node (ref "U$2") (pin "10") (pinfunction "MS2_10") (pintype "input"))
    )
    (net (code "49") (name "Net-(U$2-MS3)") (class "Default")
      (node (ref "JP7") (pin "5") (pinfunction "5_5") (pintype "passive"))
      (node (ref "U$2") (pin "11") (pinfunction "MS3_11") (pintype "bidirectional"))
    )
    (net (code "50") (name "Net-(U$2-ROSC)") (class "Default")
      (node (ref "R10") (pin "2") (pinfunction "2_2") (pintype "passive"))
      (node (ref "R11") (pin "2") (pinfunction "2_2") (pintype "passive"))
      (node (ref "U$2") (pin "13") (pinfunction "ROSC_13") (pintype "bidirectional"))
    )
    (net (code "51") (name "Net-(U$2-SENSE1)") (class "Default")
      (node (ref "R15") (pin "2") (pinfunction "2_2") (pintype "passive"))
      (node (ref "U$2") (pin "23") (pinfunction "SENSE1_23") (pintype "input"))
    )
    (net (code "52") (name "Net-(U$2-SENSE2)") (class "Default")
      (node (ref "R14") (pin "2") (pinfunction "2_2") (pintype "passive"))
      (node (ref "U$2") (pin "27") (pinfunction "SENSE2_27") (pintype "bidirectional"))
    )
    (net (code "53") (name "Net-(U$2-VCP)") (class "Default")
      (node (ref "C9") (pin "1") (pinfunction "1_1") (pintype "passive"))
      (node (ref "U$2") (pin "6") (pinfunction "VCP_6") (pintype "power_in"))
    )
    (net (code "54") (name "Net-(U$2-VREF)") (class "Default")
      (node (ref "R16") (pin "2") (pinfunction "2_2") (pintype "passive"))
      (node (ref "U$2") (pin "17") (pinfunction "VREF_17") (pintype "power_in"))
    )
    (net (code "55") (name "Net-(U$2-VREG)") (class "Default")
      (node (ref "C14") (pin "2") (pinfunction "2_2") (pintype "passive"))
      (node (ref "U$2") (pin "8") (pinfunction "VREG_8") (pintype "power_in"))
    )
    (net (code "56") (name "Net-(U$8-3V3)") (class "Default")
      (node (ref "U$8") (pin "3.3V") (pinfunction "3V3_3.3V") (pintype "bidirectional"))
      (node (ref "VDD") (pin "1") (pinfunction "1_1") (pintype "passive"))
    )
    (net (code "57") (name "Net-(U1-A0)") (class "Default")
      (node (ref "R22") (pin "2") (pinfunction "2_2") (pintype "passive"))
      (node (ref "SJ1") (pin "2") (pinfunction "2_2") (pintype "passive"))
      (node (ref "U1") (pin "7") (pinfunction "A0_7") (pintype "bidirectional"))
    )
    (net (code "58") (name "Net-(U1-A1)") (class "Default")
      (node (ref "R17") (pin "2") (pinfunction "2_2") (pintype "passive"))
      (node (ref "SJ2") (pin "2") (pinfunction "2_2") (pintype "passive"))
      (node (ref "U1") (pin "8") (pinfunction "A1_8") (pintype "bidirectional"))
    )
    (net (code "59") (name "Net-(X1-5V0)") (class "Default")
      (node (ref "5V") (pin "1") (pinfunction "1_1") (pintype "passive"))
      (node (ref "X1") (pin "2") (pinfunction "5V0_2") (pintype "power_in"))
    )
    (net (code "60") (name "Net-(X1-GPIO17)") (class "Default")
      (node (ref "ENABLE2") (pin "2") (pinfunction "2_2") (pintype "passive"))
      (node (ref "X1") (pin "11") (pinfunction "GPIO17_11") (pintype "bidirectional"))
    )
    (net (code "61") (name "Net-(X1-GPIO18)") (class "Default")
      (node (ref "ENABLE1") (pin "2") (pinfunction "2_2") (pintype "passive"))
      (node (ref "X1") (pin "12") (pinfunction "GPIO18_12") (pintype "bidirectional"))
    )
    (net (code "62") (name "Net-(X1-GPIO22)") (class "Default")
      (node (ref "STEP2") (pin "2") (pinfunction "2_2") (pintype "passive"))
      (node (ref "X1") (pin "15") (pinfunction "GPIO22_15") (pintype "bidirectional"))
    )
    (net (code "63") (name "Net-(X1-GPIO23)") (class "Default")
      (node (ref "DIR1") (pin "2") (pinfunction "2_2") (pintype "passive"))
      (node (ref "X1") (pin "16") (pinfunction "GPIO23_16") (pintype "bidirectional"))
    )
    (net (code "64") (name "Net-(X1-GPIO24)") (class "Default")
      (node (ref "DIR2") (pin "2") (pinfunction "2_2") (pintype "passive"))
      (node (ref "X1") (pin "18") (pinfunction "GPIO24_18") (pintype "bidirectional"))
    )
    (net (code "65") (name "Net-(X1-GPIO27)") (class "Default")
      (node (ref "STEP1") (pin "2") (pinfunction "2_2") (pintype "passive"))
      (node (ref "X1") (pin "13") (pinfunction "GPIO27_13") (pintype "bidirectional"))
    )
    (net (code "66") (name "Net-(X1-SCL)") (class "Default")
      (node (ref "SCL") (pin "2") (pinfunction "2_2") (pintype "passive"))
      (node (ref "X1") (pin "5") (pinfunction "SCL_5") (pintype "bidirectional"))
    )
    (net (code "67") (name "Net-(X1-SDA)") (class "Default")
      (node (ref "SDA") (pin "2") (pinfunction "2_2") (pintype "passive"))
      (node (ref "X1") (pin "3") (pinfunction "SDA_3") (pintype "bidirectional"))
    )
    (net (code "68") (name "V+") (class "Default")
      (node (ref "C10") (pin "2") (pinfunction "2_2") (pintype "passive"))
      (node (ref "C11") (pin "2") (pinfunction "2_2") (pintype "passive"))
      (node (ref "C12") (pin "2") (pinfunction "2_2") (pintype "passive"))
      (node (ref "C2") (pin "2") (pinfunction "2_2") (pintype "passive"))
      (node (ref "C3") (pin "2") (pinfunction "2_2") (pintype "passive"))
      (node (ref "C4") (pin "2") (pinfunction "2_2") (pintype "passive"))
      (node (ref "C5") (pin "2") (pinfunction "2_2") (pintype "passive"))
      (node (ref "C9") (pin "2") (pinfunction "2_2") (pintype "passive"))
      (node (ref "JP1") (pin "2") (pinfunction "2_2") (pintype "passive"))
      (node (ref "JP5") (pin "2") (pinfunction "2_2") (pintype "passive"))
      (node (ref "JP9") (pin "5") (pinfunction "5_5") (pintype "passive"))
      (node (ref "R21") (pin "1") (pinfunction "1_1") (pintype "passive"))
      (node (ref "U$1") (pin "22") (pinfunction "VBB1_22") (pintype "power_in"))
      (node (ref "U$1") (pin "28") (pinfunction "VBB2_28") (pintype "power_in"))
      (node (ref "U$2") (pin "22") (pinfunction "VBB1_22") (pintype "power_in"))
      (node (ref "U$2") (pin "28") (pinfunction "VBB2_28") (pintype "power_in"))
      (node (ref "U1") (pin "2") (pinfunction "VIN-_2") (pintype "bidirectional"))
    )
    (net (code "69") (name "VDD") (class "Default")
      (node (ref "C13") (pin "2") (pinfunction "2_2") (pintype "passive"))
      (node (ref "C16") (pin "1") (pinfunction "1_1") (pintype "passive"))
      (node (ref "C20") (pin "1") (pinfunction "1_1") (pintype "passive"))
      (node (ref "C6") (pin "2") (pinfunction "2_2") (pintype "passive"))
      (node (ref "IC3.3V") (pin "4") (pinfunction "FB_4") (pintype "open_collector"))
      (node (ref "JP2") (pin "2") (pinfunction "2_2") (pintype "passive"))
      (node (ref "JP6") (pin "2") (pinfunction "2_2") (pintype "passive"))
      (node (ref "JP9") (pin "1") (pinfunction "1_1") (pintype "passive"))
      (node (ref "L1") (pin "2") (pinfunction "2_2") (pintype "passive"))
      (node (ref "R1") (pin "1") (pinfunction "1_1") (pintype "passive"))
      (node (ref "R10") (pin "1") (pinfunction "1_1") (pintype "passive"))
      (node (ref "R13") (pin "2") (pinfunction "2_2") (pintype "passive"))
      (node (ref "R18") (pin "2") (pinfunction "2_2") (pintype "passive"))
      (node (ref "R2") (pin "1") (pinfunction "1_1") (pintype "passive"))
      (node (ref "R23") (pin "2") (pinfunction "2_2") (pintype "passive"))
      (node (ref "R5") (pin "2") (pinfunction "2_2") (pintype "passive"))
      (node (ref "R9") (pin "1") (pinfunction "1_1") (pintype "passive"))
      (node (ref "SJ1") (pin "1") (pinfunction "1_1") (pintype "passive"))
      (node (ref "SJ2") (pin "1") (pinfunction "1_1") (pintype "passive"))
      (node (ref "U$1") (pin "15") (pinfunction "VDD_15") (pintype "power_in"))
      (node (ref "U$2") (pin "15") (pinfunction "VDD_15") (pintype "power_in"))
      (node (ref "U1") (pin "4") (pinfunction "VCC_4") (pintype "bidirectional"))
      (node (ref "VDD") (pin "2") (pinfunction "2_2") (pintype "passive"))
    )
    (net (code "70") (name "unconnected-(X1-GPIO04-Pad7)") (class "Default")
      (node (ref "X1") (pin "7") (pinfunction "GPIO04_7") (pintype "bidirectional"))
    )
    (net (code "71") (name "unconnected-(X1-GPIO05-Pad29)") (class "Default")
      (node (ref "X1") (pin "29") (pinfunction "GPIO05_29") (pintype "no_connect"))
    )
    (net (code "72") (name "unconnected-(X1-GPIO06-Pad31)") (class "Default")
      (node (ref "X1") (pin "31") (pinfunction "GPIO06_31") (pintype "no_connect"))
    )
    (net (code "73") (name "unconnected-(X1-GPIO12-Pad32)") (class "Default")
      (node (ref "X1") (pin "32") (pinfunction "GPIO12_32") (pintype "no_connect"))
    )
    (net (code "74") (name "unconnected-(X1-GPIO13-Pad33)") (class "Default")
      (node (ref "X1") (pin "33") (pinfunction "GPIO13_33") (pintype "no_connect"))
    )
    (net (code "75") (name "unconnected-(X1-GPIO16-Pad36)") (class "Default")
      (node (ref "X1") (pin "36") (pinfunction "GPIO16_36") (pintype "no_connect"))
    )
    (net (code "76") (name "unconnected-(X1-GPIO19-Pad35)") (class "Default")
      (node (ref "X1") (pin "35") (pinfunction "GPIO19_35") (pintype "no_connect"))
    )
    (net (code "77") (name "unconnected-(X1-GPIO20-Pad38)") (class "Default")
      (node (ref "X1") (pin "38") (pinfunction "GPIO20_38") (pintype "no_connect"))
    )
    (net (code "78") (name "unconnected-(X1-GPIO21-Pad40)") (class "Default")
      (node (ref "X1") (pin "40") (pinfunction "GPIO21_40") (pintype "no_connect"))
    )
    (net (code "79") (name "unconnected-(X1-GPIO25-Pad22)") (class "Default")
      (node (ref "X1") (pin "22") (pinfunction "GPIO25_22") (pintype "bidirectional"))
    )
    (net (code "80") (name "unconnected-(X1-GPIO26-Pad37)") (class "Default")
      (node (ref "X1") (pin "37") (pinfunction "GPIO26_37") (pintype "no_connect"))
    )
    (net (code "81") (name "unconnected-(X1-ID_SC-Pad28)") (class "Default")
      (node (ref "X1") (pin "28") (pinfunction "ID_SC_28") (pintype "no_connect"))
    )
    (net (code "82") (name "unconnected-(X1-ID_SD-Pad27)") (class "Default")
      (node (ref "X1") (pin "27") (pinfunction "ID_SD_27") (pintype "no_connect"))
    )
    (net (code "83") (name "unconnected-(X1-N.C.0-Pad4)") (class "Default")
      (node (ref "X1") (pin "4") (pinfunction "N.C.0_4") (pintype "no_connect"))
    )
    (net (code "84") (name "unconnected-(X1-N.C.1-Pad9)") (class "Default")
      (node (ref "X1") (pin "9") (pinfunction "N.C.1_9") (pintype "no_connect"))
    )
    (net (code "85") (name "unconnected-(X1-N.C.2-Pad14)") (class "Default")
      (node (ref "X1") (pin "14") (pinfunction "N.C.2_14") (pintype "no_connect"))
    )
    (net (code "86") (name "unconnected-(X1-N.C.3-Pad17)") (class "Default")
      (node (ref "X1") (pin "17") (pinfunction "N.C.3_17") (pintype "no_connect"))
    )
    (net (code "87") (name "unconnected-(X1-N.C.4-Pad20)") (class "Default")
      (node (ref "X1") (pin "20") (pinfunction "N.C.4_20") (pintype "no_connect"))
    )
    (net (code "88") (name "unconnected-(X1-N.C.5-Pad25)") (class "Default")
      (node (ref "X1") (pin "25") (pinfunction "N.C.5_25") (pintype "no_connect"))
    )
    (net (code "89") (name "unconnected-(X1-N.C.6-Pad30)") (class "Default")
      (node (ref "X1") (pin "30") (pinfunction "N.C.6_30") (pintype "no_connect"))
    )
    (net (code "90") (name "unconnected-(X1-N.C.7-Pad34)") (class "Default")
      (node (ref "X1") (pin "34") (pinfunction "N.C.7_34") (pintype "no_connect"))
    )
    (net (code "91") (name "unconnected-(X1-N.C.8-Pad39)") (class "Default")
      (node (ref "X1") (pin "39") (pinfunction "N.C.8_39") (pintype "no_connect"))
    )
    (net (code "92") (name "unconnected-(X1-RXD-Pad10)") (class "Default")
      (node (ref "X1") (pin "10") (pinfunction "RXD_10") (pintype "bidirectional"))
    )
    (net (code "93") (name "unconnected-(X1-SPI_CE0-Pad24)") (class "Default")
      (node (ref "X1") (pin "24") (pinfunction "SPI_CE0_24") (pintype "bidirectional"))
    )
    (net (code "94") (name "unconnected-(X1-SPI_CE1-Pad26)") (class "Default")
      (node (ref "X1") (pin "26") (pinfunction "SPI_CE1_26") (pintype "bidirectional"))
    )
    (net (code "95") (name "unconnected-(X1-SPI_MISO-Pad21)") (class "Default")
      (node (ref "X1") (pin "21") (pinfunction "SPI_MISO_21") (pintype "bidirectional"))
    )
    (net (code "96") (name "unconnected-(X1-SPI_MOSI-Pad19)") (class "Default")
      (node (ref "X1") (pin "19") (pinfunction "SPI_MOSI_19") (pintype "bidirectional"))
    )
    (net (code "97") (name "unconnected-(X1-SPI_SCLK-Pad23)") (class "Default")
      (node (ref "X1") (pin "23") (pinfunction "SPI_SCLK_23") (pintype "bidirectional"))
    )
    (net (code "98") (name "unconnected-(X1-TXD-Pad8)") (class "Default")
      (node (ref "X1") (pin "8") (pinfunction "TXD_8") (pintype "bidirectional"))
    )
  )
)
